# arietta-shield.net
KiCad netlist of a schematic drawn in EAGLE
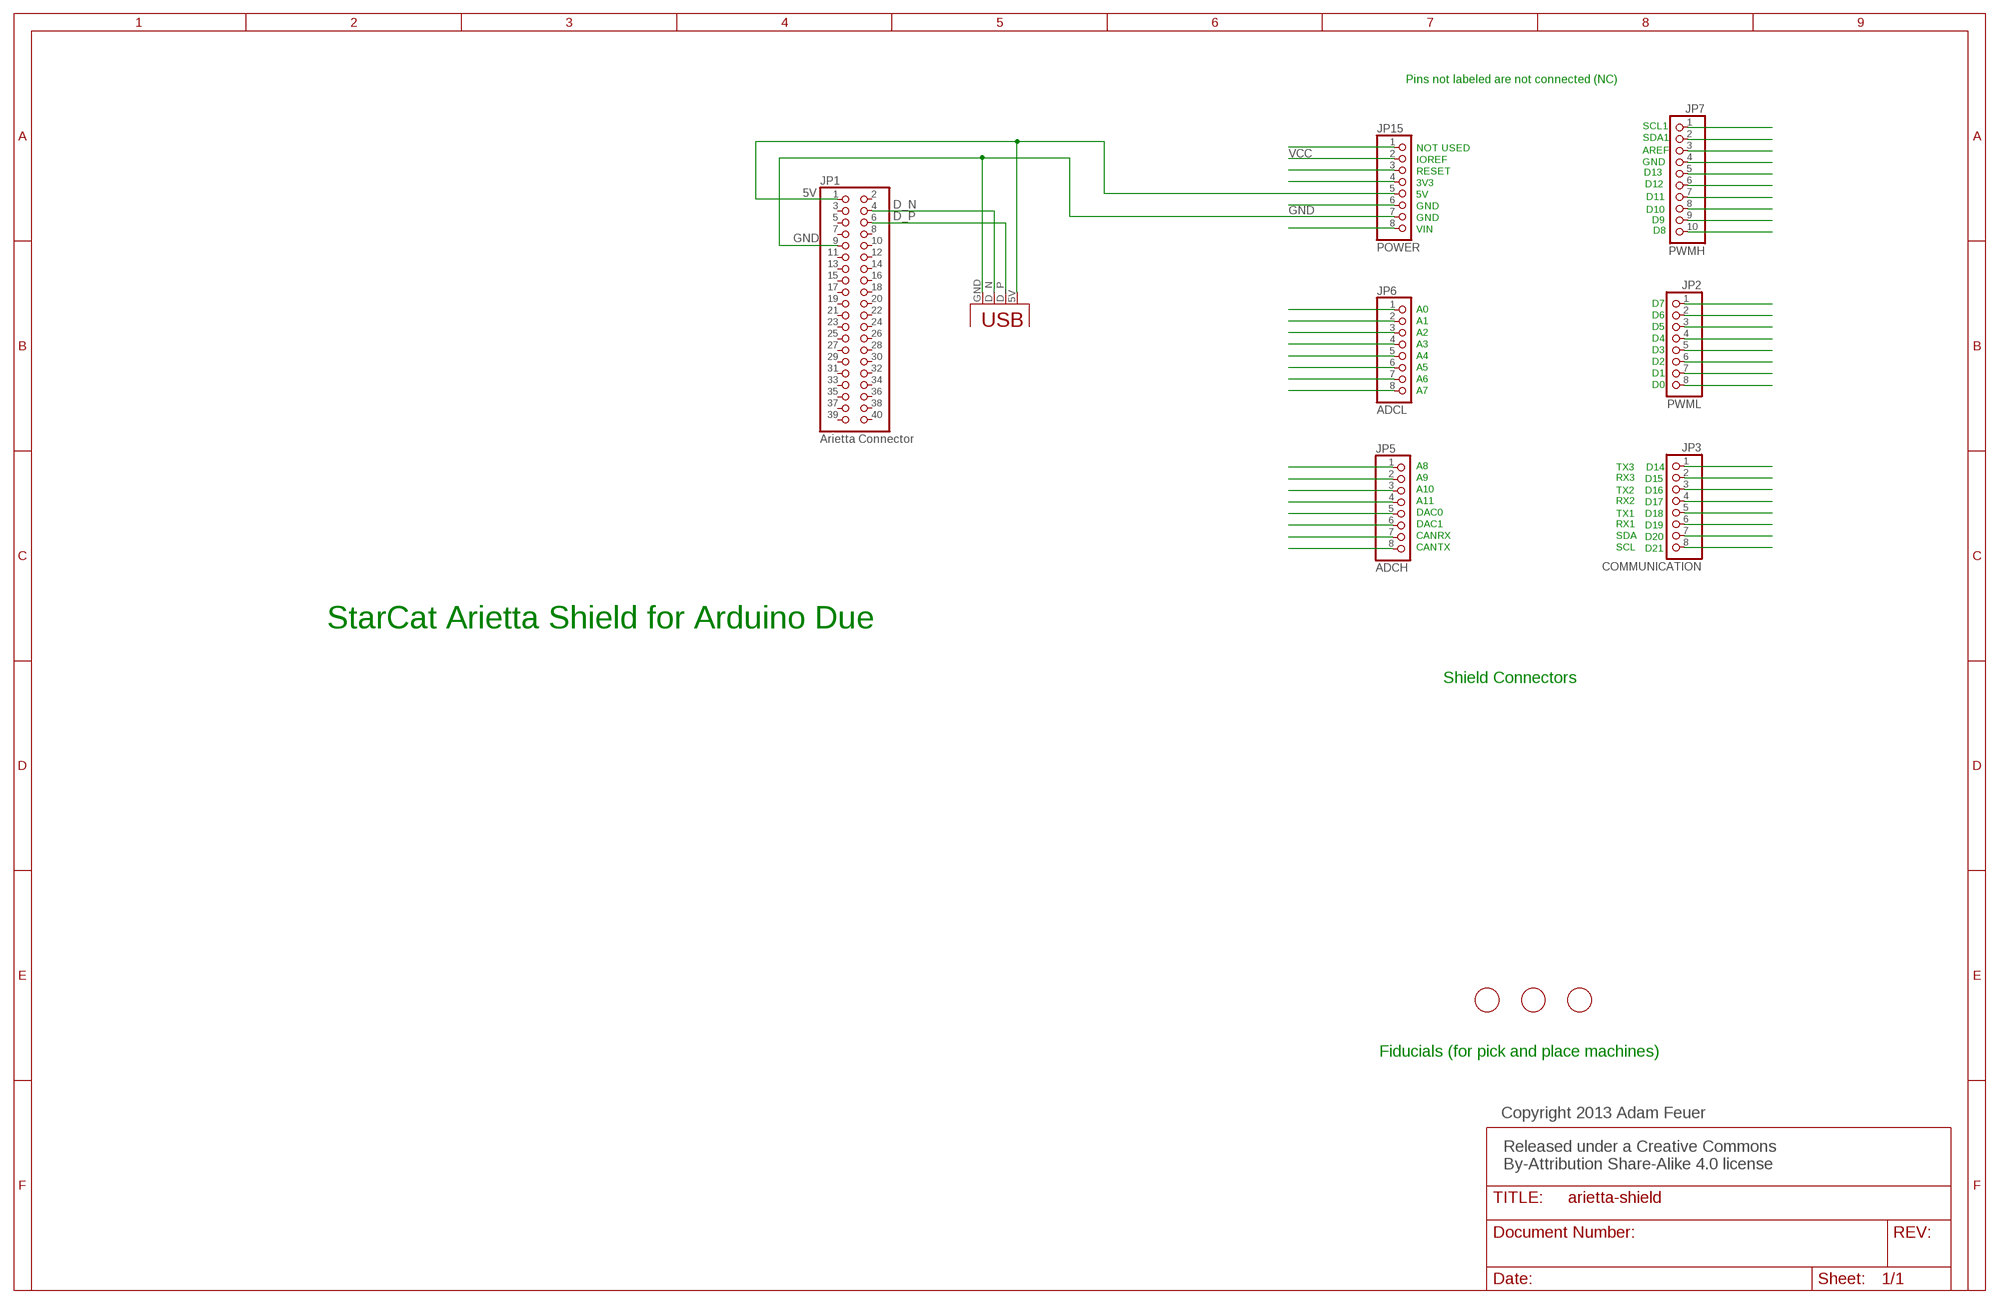
[diagram p0: schematic, sheet 1]

(export (version "E")
  (design (tool "Eeschema 10.0.6"))
  (components
    (comp (ref "JP1")
      (value "Arietta Connector")
      (footprint "eagle-import:2X20")
      (libsource (lib "eagle-import") (part "PINHD-2X20"))
    )
    (comp (ref "JP2")
      (value "PWML")
      (footprint "eagle-import:1X08")
      (libsource (lib "eagle-import") (part "PINHD-1X8"))
    )
    (comp (ref "JP3")
      (value "COMMUNICATION")
      (footprint "eagle-import:1X08")
      (libsource (lib "eagle-import") (part "PINHD-1X8"))
    )
    (comp (ref "JP5")
      (value "ADCH")
      (footprint "eagle-import:1X08")
      (libsource (lib "eagle-import") (part "PINHD-1X8"))
    )
    (comp (ref "JP6")
      (value "ADCL")
      (footprint "eagle-import:1X08")
      (libsource (lib "eagle-import") (part "PINHD-1X8"))
    )
    (comp (ref "JP7")
      (value "PWMH")
      (footprint "eagle-import:1X10")
      (libsource (lib "eagle-import") (part "PINHD-1X10"))
    )
    (comp (ref "JP15")
      (value "POWER")
      (footprint "eagle-import:1X08")
      (libsource (lib "eagle-import") (part "PINHD-1X8"))
    )
    (comp (ref "U$2")
      (value "FIDUCIAL")
      (footprint "eagle-import:FIDUCIAL_1MM")
      (libsource (lib "eagle-import") (part "FIDUCIAL"))
    )
    (comp (ref "U$5")
      (value "FIDUCIAL")
      (footprint "eagle-import:FIDUCIAL_1MM")
      (libsource (lib "eagle-import") (part "FIDUCIAL"))
    )
    (comp (ref "U$6")
      (value "FIDUCIAL")
      (footprint "eagle-import:FIDUCIAL_1MM")
      (libsource (lib "eagle-import") (part "FIDUCIAL"))
    )
    (comp (ref "U$7")
      (value "USB-A-FEMALE")
      (footprint "eagle-import:USB-A-FEMALE")
      (libsource (lib "eagle-import") (part "USB-A-FEMALE"))
    )
  )
  (nets
    (net (code "1") (name "/5V") (class "Default")
      (node (ref "JP1") (pin "1") (pinfunction "1_1") (pintype "passive"))
      (node (ref "JP15") (pin "5") (pinfunction "5_5") (pintype "passive"))
      (node (ref "U$7") (pin "5V") (pinfunction "5V_5V") (pintype "bidirectional"))
    )
    (net (code "2") (name "/D_N") (class "Default")
      (node (ref "JP1") (pin "4") (pinfunction "4_4") (pintype "passive"))
      (node (ref "U$7") (pin "D_N") (pinfunction "D_N_D_N") (pintype "bidirectional"))
    )
    (net (code "3") (name "/D_P") (class "Default")
      (node (ref "JP1") (pin "6") (pinfunction "6_6") (pintype "passive"))
      (node (ref "U$7") (pin "D_P") (pinfunction "D_P_D_P") (pintype "bidirectional"))
    )
    (net (code "4") (name "/GND") (class "Default")
      (node (ref "JP1") (pin "9") (pinfunction "9_9") (pintype "passive"))
      (node (ref "JP15") (pin "7") (pinfunction "7_7") (pintype "passive"))
      (node (ref "U$7") (pin "GND") (pinfunction "GND_GND") (pintype "bidirectional"))
    )
    (net (code "5") (name "/VCC") (class "Default")
      (node (ref "JP15") (pin "2") (pinfunction "2_2") (pintype "passive"))
    )
    (net (code "6") (name "unconnected-(JP1-Pad2)") (class "Default")
      (node (ref "JP1") (pin "2") (pinfunction "2_2") (pintype "passive"))
    )
    (net (code "7") (name "unconnected-(JP1-Pad3)") (class "Default")
      (node (ref "JP1") (pin "3") (pinfunction "3_3") (pintype "passive"))
    )
    (net (code "8") (name "unconnected-(JP1-Pad5)") (class "Default")
      (node (ref "JP1") (pin "5") (pinfunction "5_5") (pintype "passive"))
    )
    (net (code "9") (name "unconnected-(JP1-Pad7)") (class "Default")
      (node (ref "JP1") (pin "7") (pinfunction "7_7") (pintype "passive"))
    )
    (net (code "10") (name "unconnected-(JP1-Pad8)") (class "Default")
      (node (ref "JP1") (pin "8") (pinfunction "8_8") (pintype "passive"))
    )
    (net (code "11") (name "unconnected-(JP1-Pad10)") (class "Default")
      (node (ref "JP1") (pin "10") (pinfunction "10_10") (pintype "passive"))
    )
    (net (code "12") (name "unconnected-(JP1-Pad11)") (class "Default")
      (node (ref "JP1") (pin "11") (pinfunction "11_11") (pintype "passive"))
    )
    (net (code "13") (name "unconnected-(JP1-Pad12)") (class "Default")
      (node (ref "JP1") (pin "12") (pinfunction "12_12") (pintype "passive"))
    )
    (net (code "14") (name "unconnected-(JP1-Pad13)") (class "Default")
      (node (ref "JP1") (pin "13") (pinfunction "13_13") (pintype "passive"))
    )
    (net (code "15") (name "unconnected-(JP1-Pad14)") (class "Default")
      (node (ref "JP1") (pin "14") (pinfunction "14_14") (pintype "passive"))
    )
    (net (code "16") (name "unconnected-(JP1-Pad15)") (class "Default")
      (node (ref "JP1") (pin "15") (pinfunction "15_15") (pintype "passive"))
    )
    (net (code "17") (name "unconnected-(JP1-Pad16)") (class "Default")
      (node (ref "JP1") (pin "16") (pinfunction "16_16") (pintype "passive"))
    )
    (net (code "18") (name "unconnected-(JP1-Pad17)") (class "Default")
      (node (ref "JP1") (pin "17") (pinfunction "17_17") (pintype "passive"))
    )
    (net (code "19") (name "unconnected-(JP1-Pad18)") (class "Default")
      (node (ref "JP1") (pin "18") (pinfunction "18_18") (pintype "passive"))
    )
    (net (code "20") (name "unconnected-(JP1-Pad19)") (class "Default")
      (node (ref "JP1") (pin "19") (pinfunction "19_19") (pintype "passive"))
    )
    (net (code "21") (name "unconnected-(JP1-Pad20)") (class "Default")
      (node (ref "JP1") (pin "20") (pinfunction "20_20") (pintype "passive"))
    )
    (net (code "22") (name "unconnected-(JP1-Pad21)") (class "Default")
      (node (ref "JP1") (pin "21") (pinfunction "21_21") (pintype "passive"))
    )
    (net (code "23") (name "unconnected-(JP1-Pad22)") (class "Default")
      (node (ref "JP1") (pin "22") (pinfunction "22_22") (pintype "passive"))
    )
    (net (code "24") (name "unconnected-(JP1-Pad23)") (class "Default")
      (node (ref "JP1") (pin "23") (pinfunction "23_23") (pintype "passive"))
    )
    (net (code "25") (name "unconnected-(JP1-Pad24)") (class "Default")
      (node (ref "JP1") (pin "24") (pinfunction "24_24") (pintype "passive"))
    )
    (net (code "26") (name "unconnected-(JP1-Pad25)") (class "Default")
      (node (ref "JP1") (pin "25") (pinfunction "25_25") (pintype "passive"))
    )
    (net (code "27") (name "unconnected-(JP1-Pad26)") (class "Default")
      (node (ref "JP1") (pin "26") (pinfunction "26_26") (pintype "passive"))
    )
    (net (code "28") (name "unconnected-(JP1-Pad27)") (class "Default")
      (node (ref "JP1") (pin "27") (pinfunction "27_27") (pintype "passive"))
    )
    (net (code "29") (name "unconnected-(JP1-Pad28)") (class "Default")
      (node (ref "JP1") (pin "28") (pinfunction "28_28") (pintype "passive"))
    )
    (net (code "30") (name "unconnected-(JP1-Pad29)") (class "Default")
      (node (ref "JP1") (pin "29") (pinfunction "29_29") (pintype "passive"))
    )
    (net (code "31") (name "unconnected-(JP1-Pad30)") (class "Default")
      (node (ref "JP1") (pin "30") (pinfunction "30_30") (pintype "passive"))
    )
    (net (code "32") (name "unconnected-(JP1-Pad31)") (class "Default")
      (node (ref "JP1") (pin "31") (pinfunction "31_31") (pintype "passive"))
    )
    (net (code "33") (name "unconnected-(JP1-Pad32)") (class "Default")
      (node (ref "JP1") (pin "32") (pinfunction "32_32") (pintype "passive"))
    )
    (net (code "34") (name "unconnected-(JP1-Pad33)") (class "Default")
      (node (ref "JP1") (pin "33") (pinfunction "33_33") (pintype "passive"))
    )
    (net (code "35") (name "unconnected-(JP1-Pad34)") (class "Default")
      (node (ref "JP1") (pin "34") (pinfunction "34_34") (pintype "passive"))
    )
    (net (code "36") (name "unconnected-(JP1-Pad35)") (class "Default")
      (node (ref "JP1") (pin "35") (pinfunction "35_35") (pintype "passive"))
    )
    (net (code "37") (name "unconnected-(JP1-Pad36)") (class "Default")
      (node (ref "JP1") (pin "36") (pinfunction "36_36") (pintype "passive"))
    )
    (net (code "38") (name "unconnected-(JP1-Pad37)") (class "Default")
      (node (ref "JP1") (pin "37") (pinfunction "37_37") (pintype "passive"))
    )
    (net (code "39") (name "unconnected-(JP1-Pad38)") (class "Default")
      (node (ref "JP1") (pin "38") (pinfunction "38_38") (pintype "passive"))
    )
    (net (code "40") (name "unconnected-(JP1-Pad39)") (class "Default")
      (node (ref "JP1") (pin "39") (pinfunction "39_39") (pintype "passive"))
    )
    (net (code "41") (name "unconnected-(JP1-Pad40)") (class "Default")
      (node (ref "JP1") (pin "40") (pinfunction "40_40") (pintype "passive"))
    )
    (net (code "42") (name "unconnected-(JP2-Pad1)") (class "Default")
      (node (ref "JP2") (pin "1") (pinfunction "1_1") (pintype "passive"))
    )
    (net (code "43") (name "unconnected-(JP2-Pad2)") (class "Default")
      (node (ref "JP2") (pin "2") (pinfunction "2_2") (pintype "passive"))
    )
    (net (code "44") (name "unconnected-(JP2-Pad3)") (class "Default")
      (node (ref "JP2") (pin "3") (pinfunction "3_3") (pintype "passive"))
    )
    (net (code "45") (name "unconnected-(JP2-Pad4)") (class "Default")
      (node (ref "JP2") (pin "4") (pinfunction "4_4") (pintype "passive"))
    )
    (net (code "46") (name "unconnected-(JP2-Pad5)") (class "Default")
      (node (ref "JP2") (pin "5") (pinfunction "5_5") (pintype "passive"))
    )
    (net (code "47") (name "unconnected-(JP2-Pad6)") (class "Default")
      (node (ref "JP2") (pin "6") (pinfunction "6_6") (pintype "passive"))
    )
    (net (code "48") (name "unconnected-(JP2-Pad7)") (class "Default")
      (node (ref "JP2") (pin "7") (pinfunction "7_7") (pintype "passive"))
    )
    (net (code "49") (name "unconnected-(JP2-Pad8)") (class "Default")
      (node (ref "JP2") (pin "8") (pinfunction "8_8") (pintype "passive"))
    )
    (net (code "50") (name "unconnected-(JP3-Pad1)") (class "Default")
      (node (ref "JP3") (pin "1") (pinfunction "1_1") (pintype "passive"))
    )
    (net (code "51") (name "unconnected-(JP3-Pad2)") (class "Default")
      (node (ref "JP3") (pin "2") (pinfunction "2_2") (pintype "passive"))
    )
    (net (code "52") (name "unconnected-(JP3-Pad3)") (class "Default")
      (node (ref "JP3") (pin "3") (pinfunction "3_3") (pintype "passive"))
    )
    (net (code "53") (name "unconnected-(JP3-Pad4)") (class "Default")
      (node (ref "JP3") (pin "4") (pinfunction "4_4") (pintype "passive"))
    )
    (net (code "54") (name "unconnected-(JP3-Pad5)") (class "Default")
      (node (ref "JP3") (pin "5") (pinfunction "5_5") (pintype "passive"))
    )
    (net (code "55") (name "unconnected-(JP3-Pad6)") (class "Default")
      (node (ref "JP3") (pin "6") (pinfunction "6_6") (pintype "passive"))
    )
    (net (code "56") (name "unconnected-(JP3-Pad7)") (class "Default")
      (node (ref "JP3") (pin "7") (pinfunction "7_7") (pintype "passive"))
    )
    (net (code "57") (name "unconnected-(JP3-Pad8)") (class "Default")
      (node (ref "JP3") (pin "8") (pinfunction "8_8") (pintype "passive"))
    )
    (net (code "58") (name "unconnected-(JP5-Pad1)") (class "Default")
      (node (ref "JP5") (pin "1") (pinfunction "1_1") (pintype "passive"))
    )
    (net (code "59") (name "unconnected-(JP5-Pad2)") (class "Default")
      (node (ref "JP5") (pin "2") (pinfunction "2_2") (pintype "passive"))
    )
    (net (code "60") (name "unconnected-(JP5-Pad3)") (class "Default")
      (node (ref "JP5") (pin "3") (pinfunction "3_3") (pintype "passive"))
    )
    (net (code "61") (name "unconnected-(JP5-Pad4)") (class "Default")
      (node (ref "JP5") (pin "4") (pinfunction "4_4") (pintype "passive"))
    )
    (net (code "62") (name "unconnected-(JP5-Pad5)") (class "Default")
      (node (ref "JP5") (pin "5") (pinfunction "5_5") (pintype "passive"))
    )
    (net (code "63") (name "unconnected-(JP5-Pad6)") (class "Default")
      (node (ref "JP5") (pin "6") (pinfunction "6_6") (pintype "passive"))
    )
    (net (code "64") (name "unconnected-(JP5-Pad7)") (class "Default")
      (node (ref "JP5") (pin "7") (pinfunction "7_7") (pintype "passive"))
    )
    (net (code "65") (name "unconnected-(JP5-Pad8)") (class "Default")
      (node (ref "JP5") (pin "8") (pinfunction "8_8") (pintype "passive"))
    )
    (net (code "66") (name "unconnected-(JP6-Pad1)") (class "Default")
      (node (ref "JP6") (pin "1") (pinfunction "1_1") (pintype "passive"))
    )
    (net (code "67") (name "unconnected-(JP6-Pad2)") (class "Default")
      (node (ref "JP6") (pin "2") (pinfunction "2_2") (pintype "passive"))
    )
    (net (code "68") (name "unconnected-(JP6-Pad3)") (class "Default")
      (node (ref "JP6") (pin "3") (pinfunction "3_3") (pintype "passive"))
    )
    (net (code "69") (name "unconnected-(JP6-Pad4)") (class "Default")
      (node (ref "JP6") (pin "4") (pinfunction "4_4") (pintype "passive"))
    )
    (net (code "70") (name "unconnected-(JP6-Pad5)") (class "Default")
      (node (ref "JP6") (pin "5") (pinfunction "5_5") (pintype "passive"))
    )
    (net (code "71") (name "unconnected-(JP6-Pad6)") (class "Default")
      (node (ref "JP6") (pin "6") (pinfunction "6_6") (pintype "passive"))
    )
    (net (code "72") (name "unconnected-(JP6-Pad7)") (class "Default")
      (node (ref "JP6") (pin "7") (pinfunction "7_7") (pintype "passive"))
    )
    (net (code "73") (name "unconnected-(JP6-Pad8)") (class "Default")
      (node (ref "JP6") (pin "8") (pinfunction "8_8") (pintype "passive"))
    )
    (net (code "74") (name "unconnected-(JP7-Pad1)") (class "Default")
      (node (ref "JP7") (pin "1") (pinfunction "1_1") (pintype "passive"))
    )
    (net (code "75") (name "unconnected-(JP7-Pad2)") (class "Default")
      (node (ref "JP7") (pin "2") (pinfunction "2_2") (pintype "passive"))
    )
    (net (code "76") (name "unconnected-(JP7-Pad3)") (class "Default")
      (node (ref "JP7") (pin "3") (pinfunction "3_3") (pintype "passive"))
    )
    (net (code "77") (name "unconnected-(JP7-Pad4)") (class "Default")
      (node (ref "JP7") (pin "4") (pinfunction "4_4") (pintype "passive"))
    )
    (net (code "78") (name "unconnected-(JP7-Pad5)") (class "Default")
      (node (ref "JP7") (pin "5") (pinfunction "5_5") (pintype "passive"))
    )
    (net (code "79") (name "unconnected-(JP7-Pad6)") (class "Default")
      (node (ref "JP7") (pin "6") (pinfunction "6_6") (pintype "passive"))
    )
    (net (code "80") (name "unconnected-(JP7-Pad7)") (class "Default")
      (node (ref "JP7") (pin "7") (pinfunction "7_7") (pintype "passive"))
    )
    (net (code "81") (name "unconnected-(JP7-Pad8)") (class "Default")
      (node (ref "JP7") (pin "8") (pinfunction "8_8") (pintype "passive"))
    )
    (net (code "82") (name "unconnected-(JP7-Pad9)") (class "Default")
      (node (ref "JP7") (pin "9") (pinfunction "9_9") (pintype "passive"))
    )
    (net (code "83") (name "unconnected-(JP7-Pad10)") (class "Default")
      (node (ref "JP7") (pin "10") (pinfunction "10_10") (pintype "passive"))
    )
    (net (code "84") (name "unconnected-(JP15-Pad1)") (class "Default")
      (node (ref "JP15") (pin "1") (pinfunction "1_1") (pintype "passive"))
    )
    (net (code "85") (name "unconnected-(JP15-Pad3)") (class "Default")
      (node (ref "JP15") (pin "3") (pinfunction "3_3") (pintype "passive"))
    )
    (net (code "86") (name "unconnected-(JP15-Pad4)") (class "Default")
      (node (ref "JP15") (pin "4") (pinfunction "4_4") (pintype "passive"))
    )
    (net (code "87") (name "unconnected-(JP15-Pad6)") (class "Default")
      (node (ref "JP15") (pin "6") (pinfunction "6_6") (pintype "passive"))
    )
    (net (code "88") (name "unconnected-(JP15-Pad8)") (class "Default")
      (node (ref "JP15") (pin "8") (pinfunction "8_8") (pintype "passive"))
    )
  )
)
